# 7-GPS.net
KiCad netlist of a schematic drawn in Altium Designer
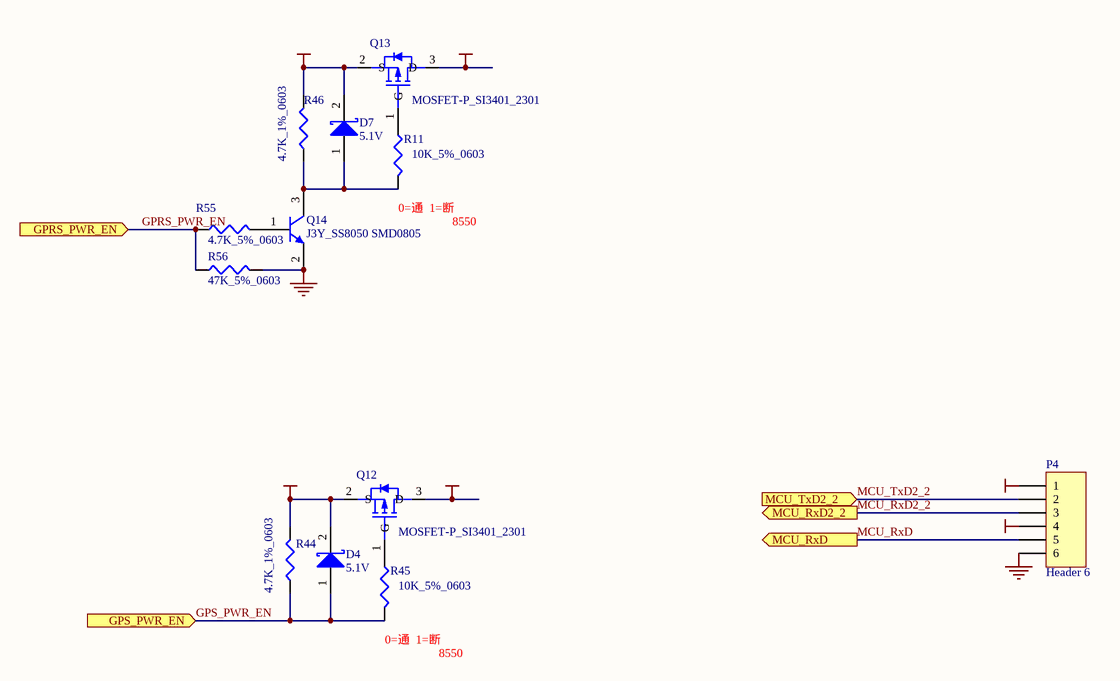
[diagram p0: 7-GPS.SCHDOC]

(export (version "E")
  (design (tool "Eeschema 10.0.6"))
  (components
    (comp (ref "D4")
      (value "5.1V")
      (footprint "LED0805")
      (description "Schottky Diode")
      (fields (field (name "PUBLISHER") "Altium Limited"))
      (libsource (lib "Miscellaneous Devices") (part "D Schottky"))
    )
    (comp (ref "D7")
      (value "5.1V")
      (footprint "LED0805")
      (description "Schottky Diode")
      (fields (field (name "PUBLISHER") "Altium Limited"))
      (libsource (lib "Miscellaneous Devices") (part "D Schottky"))
    )
    (comp (ref "P4")
      (value "Header 6")
      (footprint "HDR1X6")
      (description "Header, 6-Pin")
      (fields (field (name "PUBLISHER") "Altium Limited"))
      (libsource (lib "Miscellaneous Connectors") (part "Header 6"))
    )
    (comp (ref "Q12")
      (value "MOSFET-P_SI3401_2301")
      (footprint "SO-G3/C2.5")
      (libsource (lib "Device") (part "MOSFET-P"))
    )
    (comp (ref "Q13")
      (value "MOSFET-P_SI3401_2301")
      (footprint "SO-G3/C2.5")
      (libsource (lib "Device") (part "MOSFET-P"))
    )
    (comp (ref "Q14")
      (value "J3Y_SS8050 SMD0805")
      (footprint "SO-G3/C2.5")
      (description "NPN Bipolar Transistor")
      (fields (field (name "PUBLISHER") "Altium Limited"))
      (libsource (lib "Miscellaneous Devices") (part "QNPN"))
    )
    (comp (ref "R11")
      (value "10K_5%_0603")
      (footprint "C1608-0603")
      (description "Resistor")
      (fields (field (name "PUBLISHER") "Altium Limited"))
      (libsource (lib "Miscellaneous Devices") (part "Res3"))
    )
    (comp (ref "R44")
      (value "4.7K_1%_0603")
      (footprint "C1608-0603")
      (description "Resistor")
      (fields (field (name "PUBLISHER") "Altium Limited"))
      (libsource (lib "Miscellaneous Devices") (part "Res3"))
    )
    (comp (ref "R45")
      (value "10K_5%_0603")
      (footprint "C1608-0603")
      (description "Resistor")
      (fields (field (name "PUBLISHER") "Altium Limited"))
      (libsource (lib "Miscellaneous Devices") (part "Res3"))
    )
    (comp (ref "R46")
      (value "4.7K_1%_0603")
      (footprint "C1608-0603")
      (description "Resistor")
      (fields (field (name "PUBLISHER") "Altium Limited"))
      (libsource (lib "Miscellaneous Devices") (part "Res3"))
    )
    (comp (ref "R55")
      (value "4.7K_5%_0603")
      (footprint "C1608-0603")
      (description "Resistor")
      (libsource (lib "*") (part "RES"))
    )
    (comp (ref "R56")
      (value "47K_5%_0603")
      (footprint "C1608-0603")
      (description "Resistor")
      (libsource (lib "*") (part "RES"))
    )
  )
  (nets
    (net (code "1") (name "/GPRS_PWR_EN") (class "Default")
      (node (ref "R55") (pin "1") (pinfunction "TOP_1") (pintype "passive"))
      (node (ref "R56") (pin "1") (pinfunction "TOP_1") (pintype "passive"))
    )
    (net (code "2") (name "/GPS_PWR_EN") (class "Default")
      (node (ref "D4") (pin "1") (pinfunction "A_1") (pintype "passive"))
      (node (ref "R44") (pin "1") (pinfunction "1_1") (pintype "passive"))
      (node (ref "R45") (pin "2") (pinfunction "2_2") (pintype "passive"))
    )
    (net (code "3") (name "/MCU_RxD") (class "Default")
      (node (ref "P4") (pin "5") (pinfunction "5_5") (pintype "passive"))
    )
    (net (code "4") (name "/MCU_RxD2_2") (class "Default")
      (node (ref "P4") (pin "3") (pinfunction "3_3") (pintype "passive"))
    )
    (net (code "5") (name "/MCU_TxD2_2") (class "Default")
      (node (ref "P4") (pin "2") (pinfunction "2_2") (pintype "passive"))
    )
    (net (code "6") (name "GND") (class "Default")
      (node (ref "P4") (pin "6") (pinfunction "6_6") (pintype "passive"))
      (node (ref "Q14") (pin "2") (pinfunction "E_2") (pintype "passive"))
      (node (ref "R56") (pin "2") (pinfunction "BOT_2") (pintype "passive"))
    )
    (net (code "7") (name "Net-(D7-A)") (class "Default")
      (node (ref "D7") (pin "1") (pinfunction "A_1") (pintype "passive"))
      (node (ref "Q14") (pin "3") (pinfunction "C_3") (pintype "passive"))
      (node (ref "R11") (pin "2") (pinfunction "2_2") (pintype "passive"))
      (node (ref "R46") (pin "1") (pinfunction "1_1") (pintype "passive"))
    )
    (net (code "8") (name "Net-(Q12-G)") (class "Default")
      (node (ref "Q12") (pin "1") (pinfunction "G_1") (pintype "passive"))
      (node (ref "R45") (pin "1") (pinfunction "1_1") (pintype "passive"))
    )
    (net (code "9") (name "Net-(Q13-G)") (class "Default")
      (node (ref "Q13") (pin "1") (pinfunction "G_1") (pintype "passive"))
      (node (ref "R11") (pin "1") (pinfunction "1_1") (pintype "passive"))
    )
    (net (code "10") (name "Net-(Q14-B)") (class "Default")
      (node (ref "Q14") (pin "1") (pinfunction "B_1") (pintype "passive"))
      (node (ref "R55") (pin "2") (pinfunction "BOT_2") (pintype "passive"))
    )
    (net (code "11") (name "VCC_2V8") (class "Default")
      (node (ref "D4") (pin "2") (pinfunction "K_2") (pintype "passive"))
      (node (ref "Q12") (pin "2") (pinfunction "S_2") (pintype "passive"))
      (node (ref "R44") (pin "2") (pinfunction "2_2") (pintype "passive"))
    )
    (net (code "12") (name "VCC_MNG") (class "Default")
      (node (ref "D7") (pin "2") (pinfunction "K_2") (pintype "passive"))
      (node (ref "Q13") (pin "2") (pinfunction "S_2") (pintype "passive"))
      (node (ref "R46") (pin "2") (pinfunction "2_2") (pintype "passive"))
    )
    (net (code "13") (name "V_GPRS") (class "Default")
      (node (ref "P4") (pin "1") (pinfunction "1_1") (pintype "passive"))
      (node (ref "Q13") (pin "3") (pinfunction "D_3") (pintype "passive"))
    )
    (net (code "14") (name "V_GPS") (class "Default")
      (node (ref "P4") (pin "4") (pinfunction "4_4") (pintype "passive"))
      (node (ref "Q12") (pin "3") (pinfunction "D_3") (pintype "passive"))
    )
  )
)
